# dcb_top.net
KiCad netlist of a schematic drawn in Altium Designer
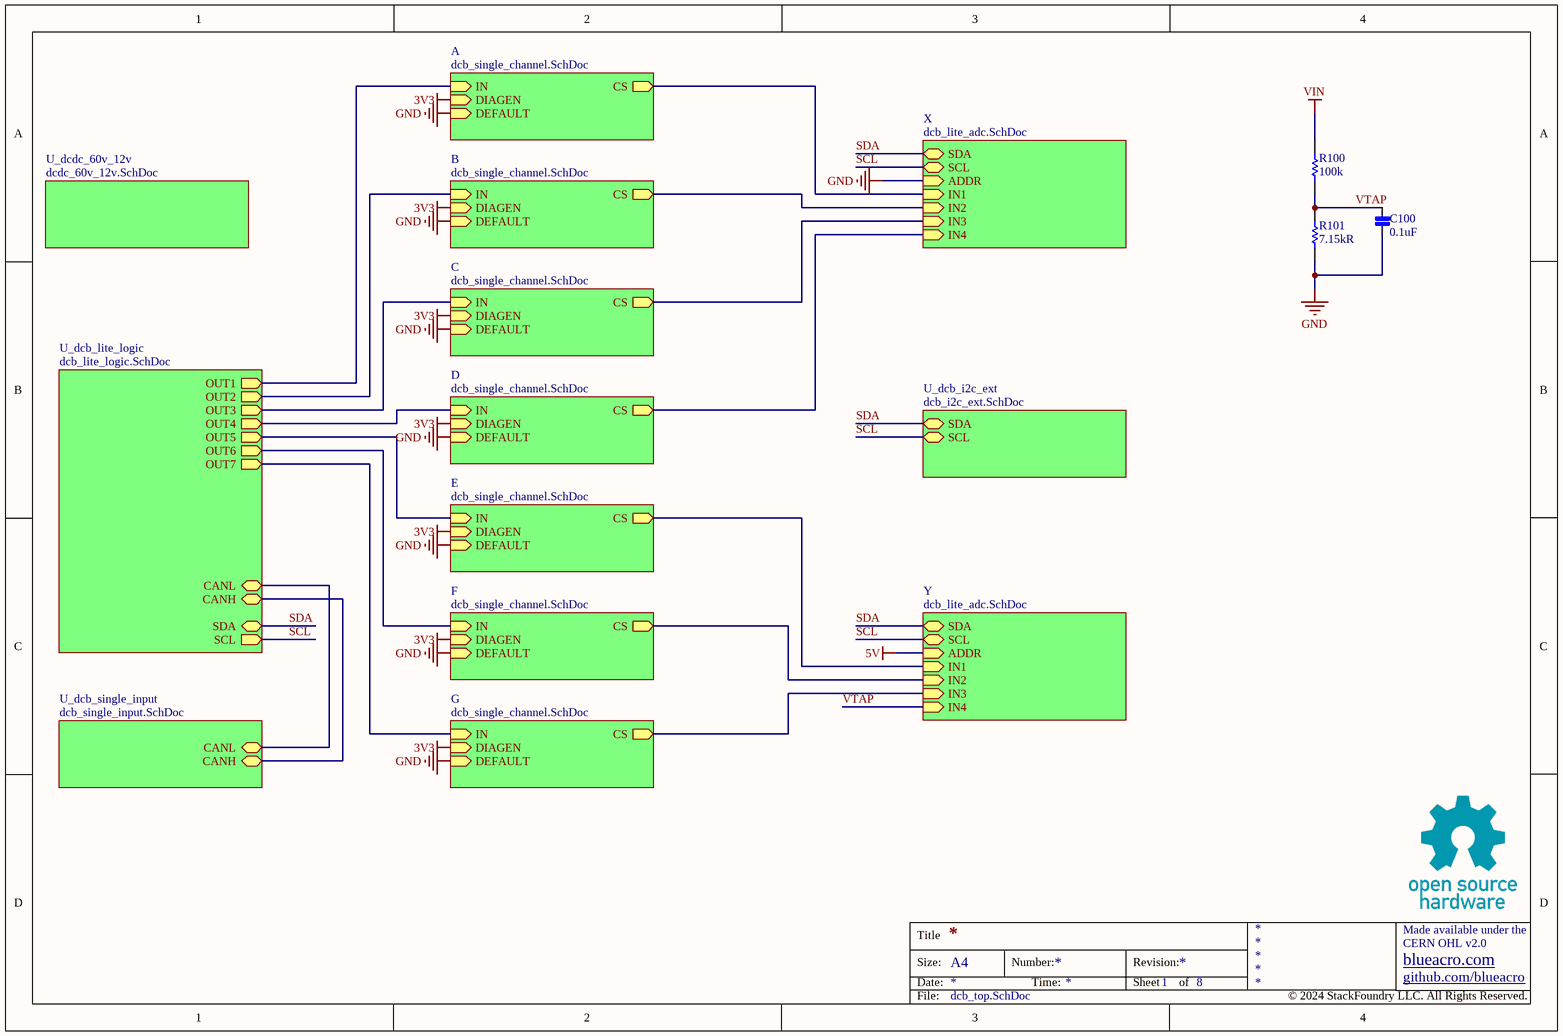
[diagram p0: dcb_top.SchDoc]

(export (version "E")
  (design (tool "Eeschema 10.0.6"))
  (components
    (comp (ref "C100")
      (value "0.1uF")
      (footprint "FP-CL10-IPC_B")
      (description "Cap Ceramic 0.1uF 50V X7R 20% SMD 0603 125C Paper T/R")
      (fields (field (name "VOLTAGE") "50V") (field (name "Comment") "CAP 0.1uF 50V X7R 0603"))
      (libsource (lib "StackFoundry LLC") (part "C-EU"))
    )
    (comp (ref "R100")
      (value "100k")
      (footprint "RESC1608-IPC-LL")
      (description "SMD Chip Resistor, 100 kOhm, ± 1%, 100 mW, 0603 [1608 Metric], Thick Film, General Purpose")
      (fields (field (name "TOLERANCE") "1%") (field (name "Comment") "100k 0603 1%"))
      (libsource (lib "StackFoundry LLC") (part "RES"))
    )
    (comp (ref "R101")
      (value "7.15kR")
      (footprint "RESC1608X55X30NL20T20")
      (description "Res Thin Film 0603 7.15K Ohm 0.1% 1/10W ±25ppm/°C Molded SMD SMD Punched Carrier T/R")
      (fields (field (name "Comment") "7.15k 0603 0.1%"))
      (libsource (lib "StackFoundry LLC") (part "RES"))
    )
  )
  (nets
    (net (code "19") (name "/VTAP") (class "Default")
      (node (ref "C100") (pin "1") (pinfunction "1_1") (pintype "passive"))
      (node (ref "R100") (pin "1") (pinfunction "1_1") (pintype "passive"))
      (node (ref "R101") (pin "2") (pinfunction "2_2") (pintype "passive"))
    )
    (net (code "22") (name "GND") (class "Default")
      (node (ref "C100") (pin "2") (pinfunction "2_2") (pintype "passive"))
      (node (ref "R101") (pin "1") (pinfunction "1_1") (pintype "passive"))
    )
    (net (code "23") (name "VIN") (class "Default")
      (node (ref "R100") (pin "2") (pinfunction "2_2") (pintype "passive"))
    )
  )
)
